# H12R10.net
KiCad netlist of a schematic drawn in EAGLE
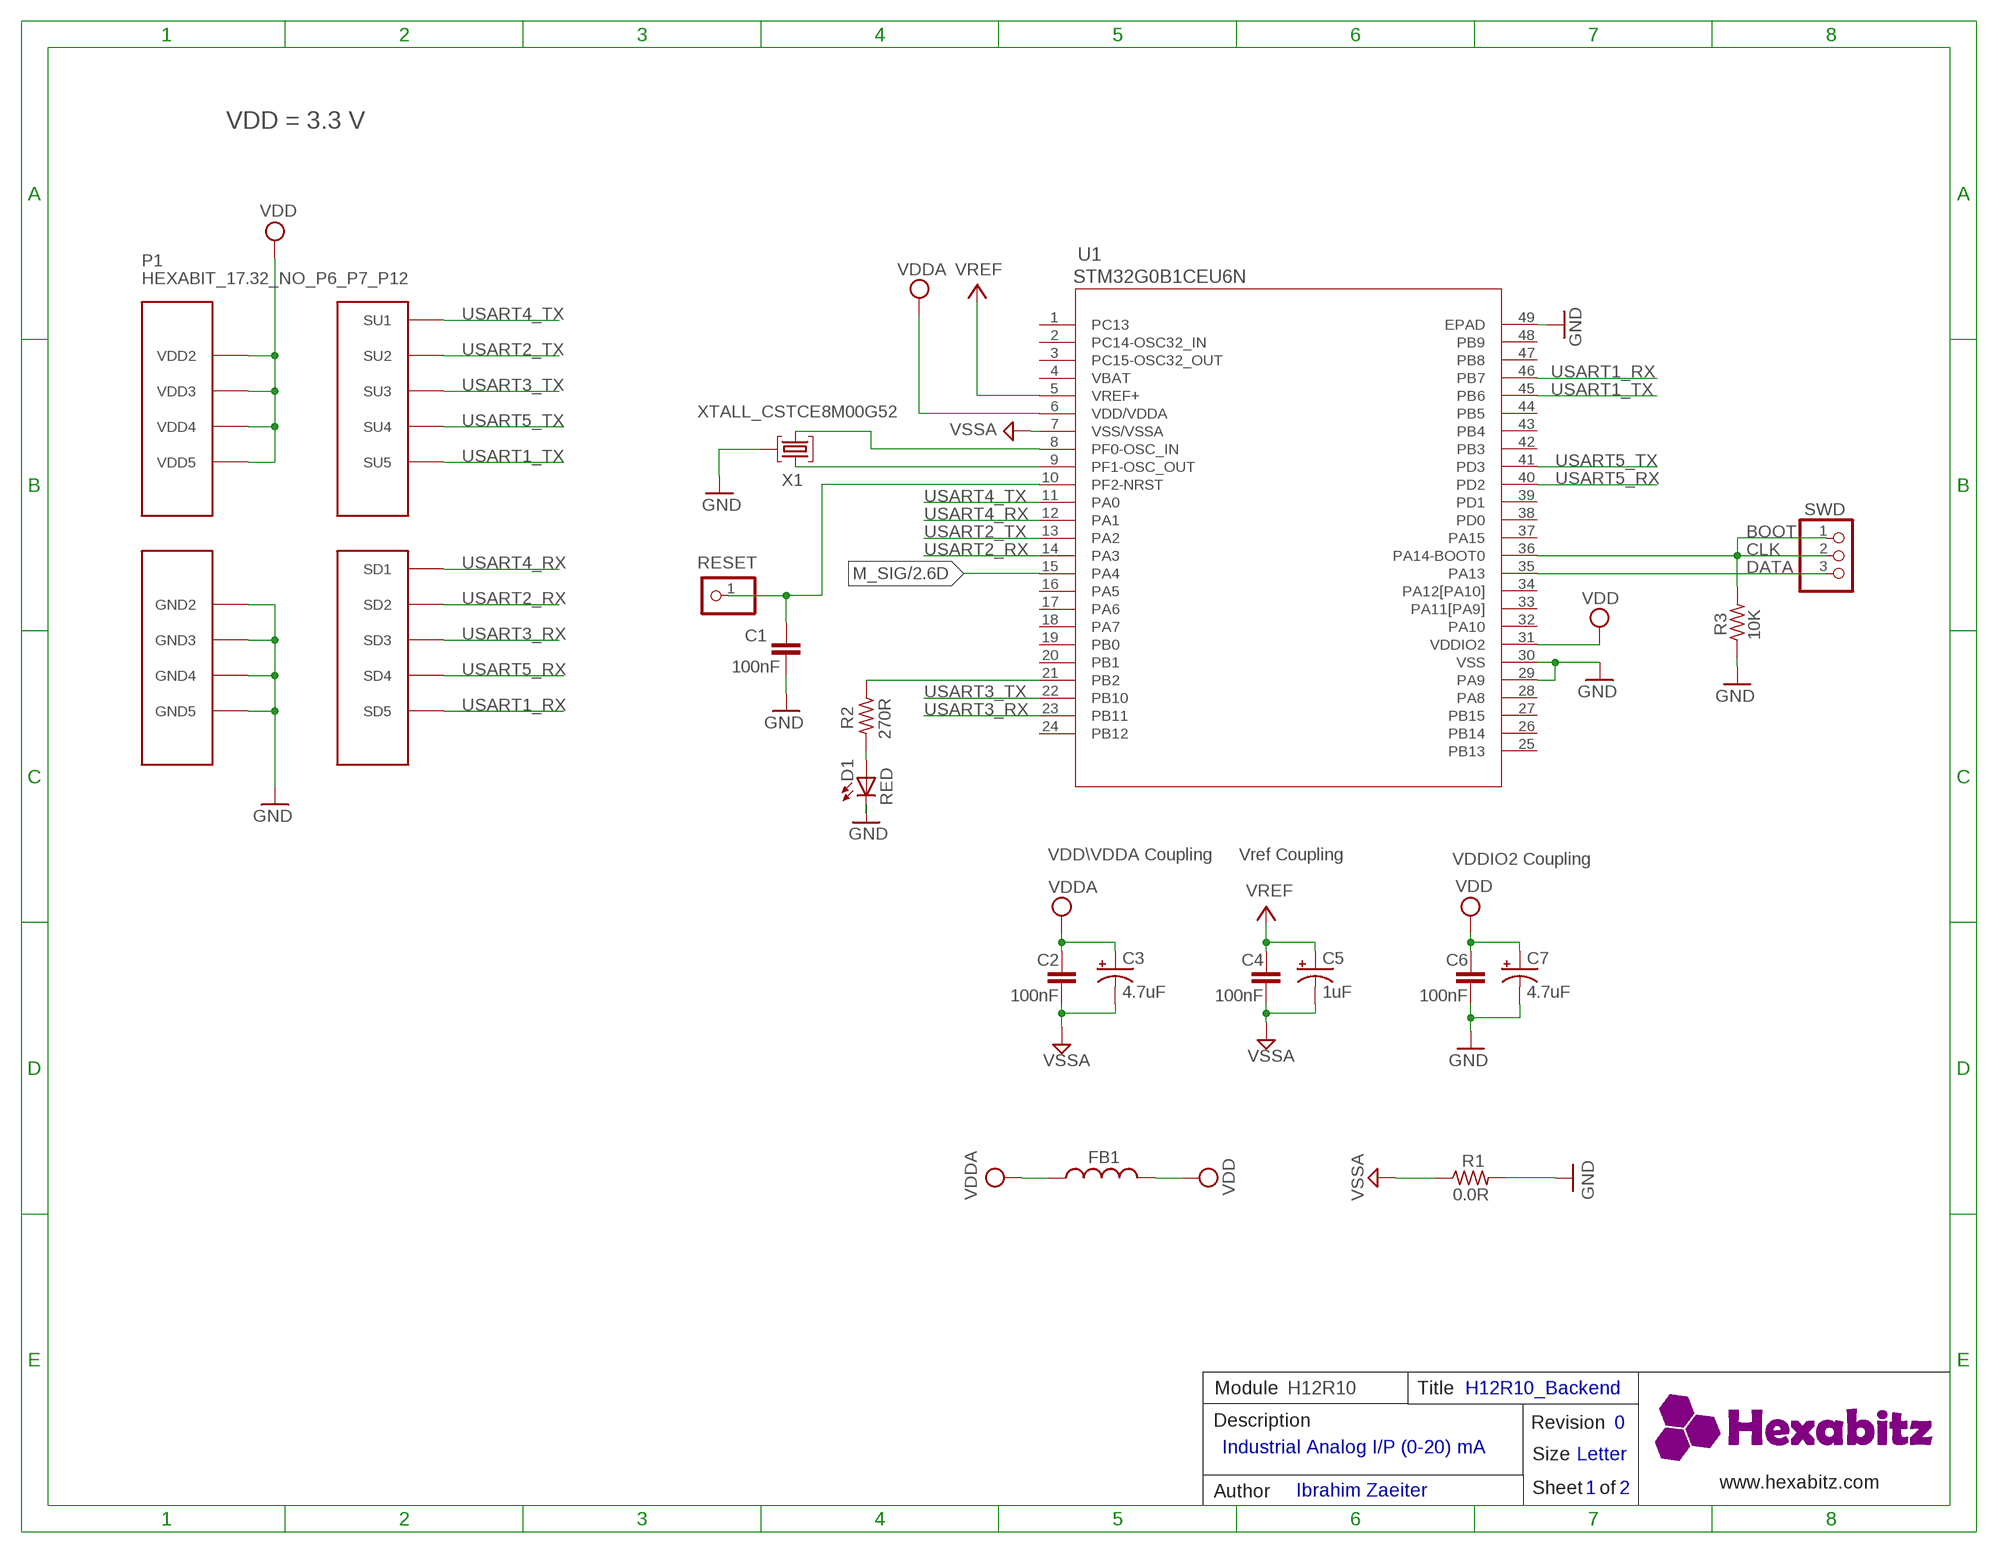
[diagram p0: schematic, sheet 1]
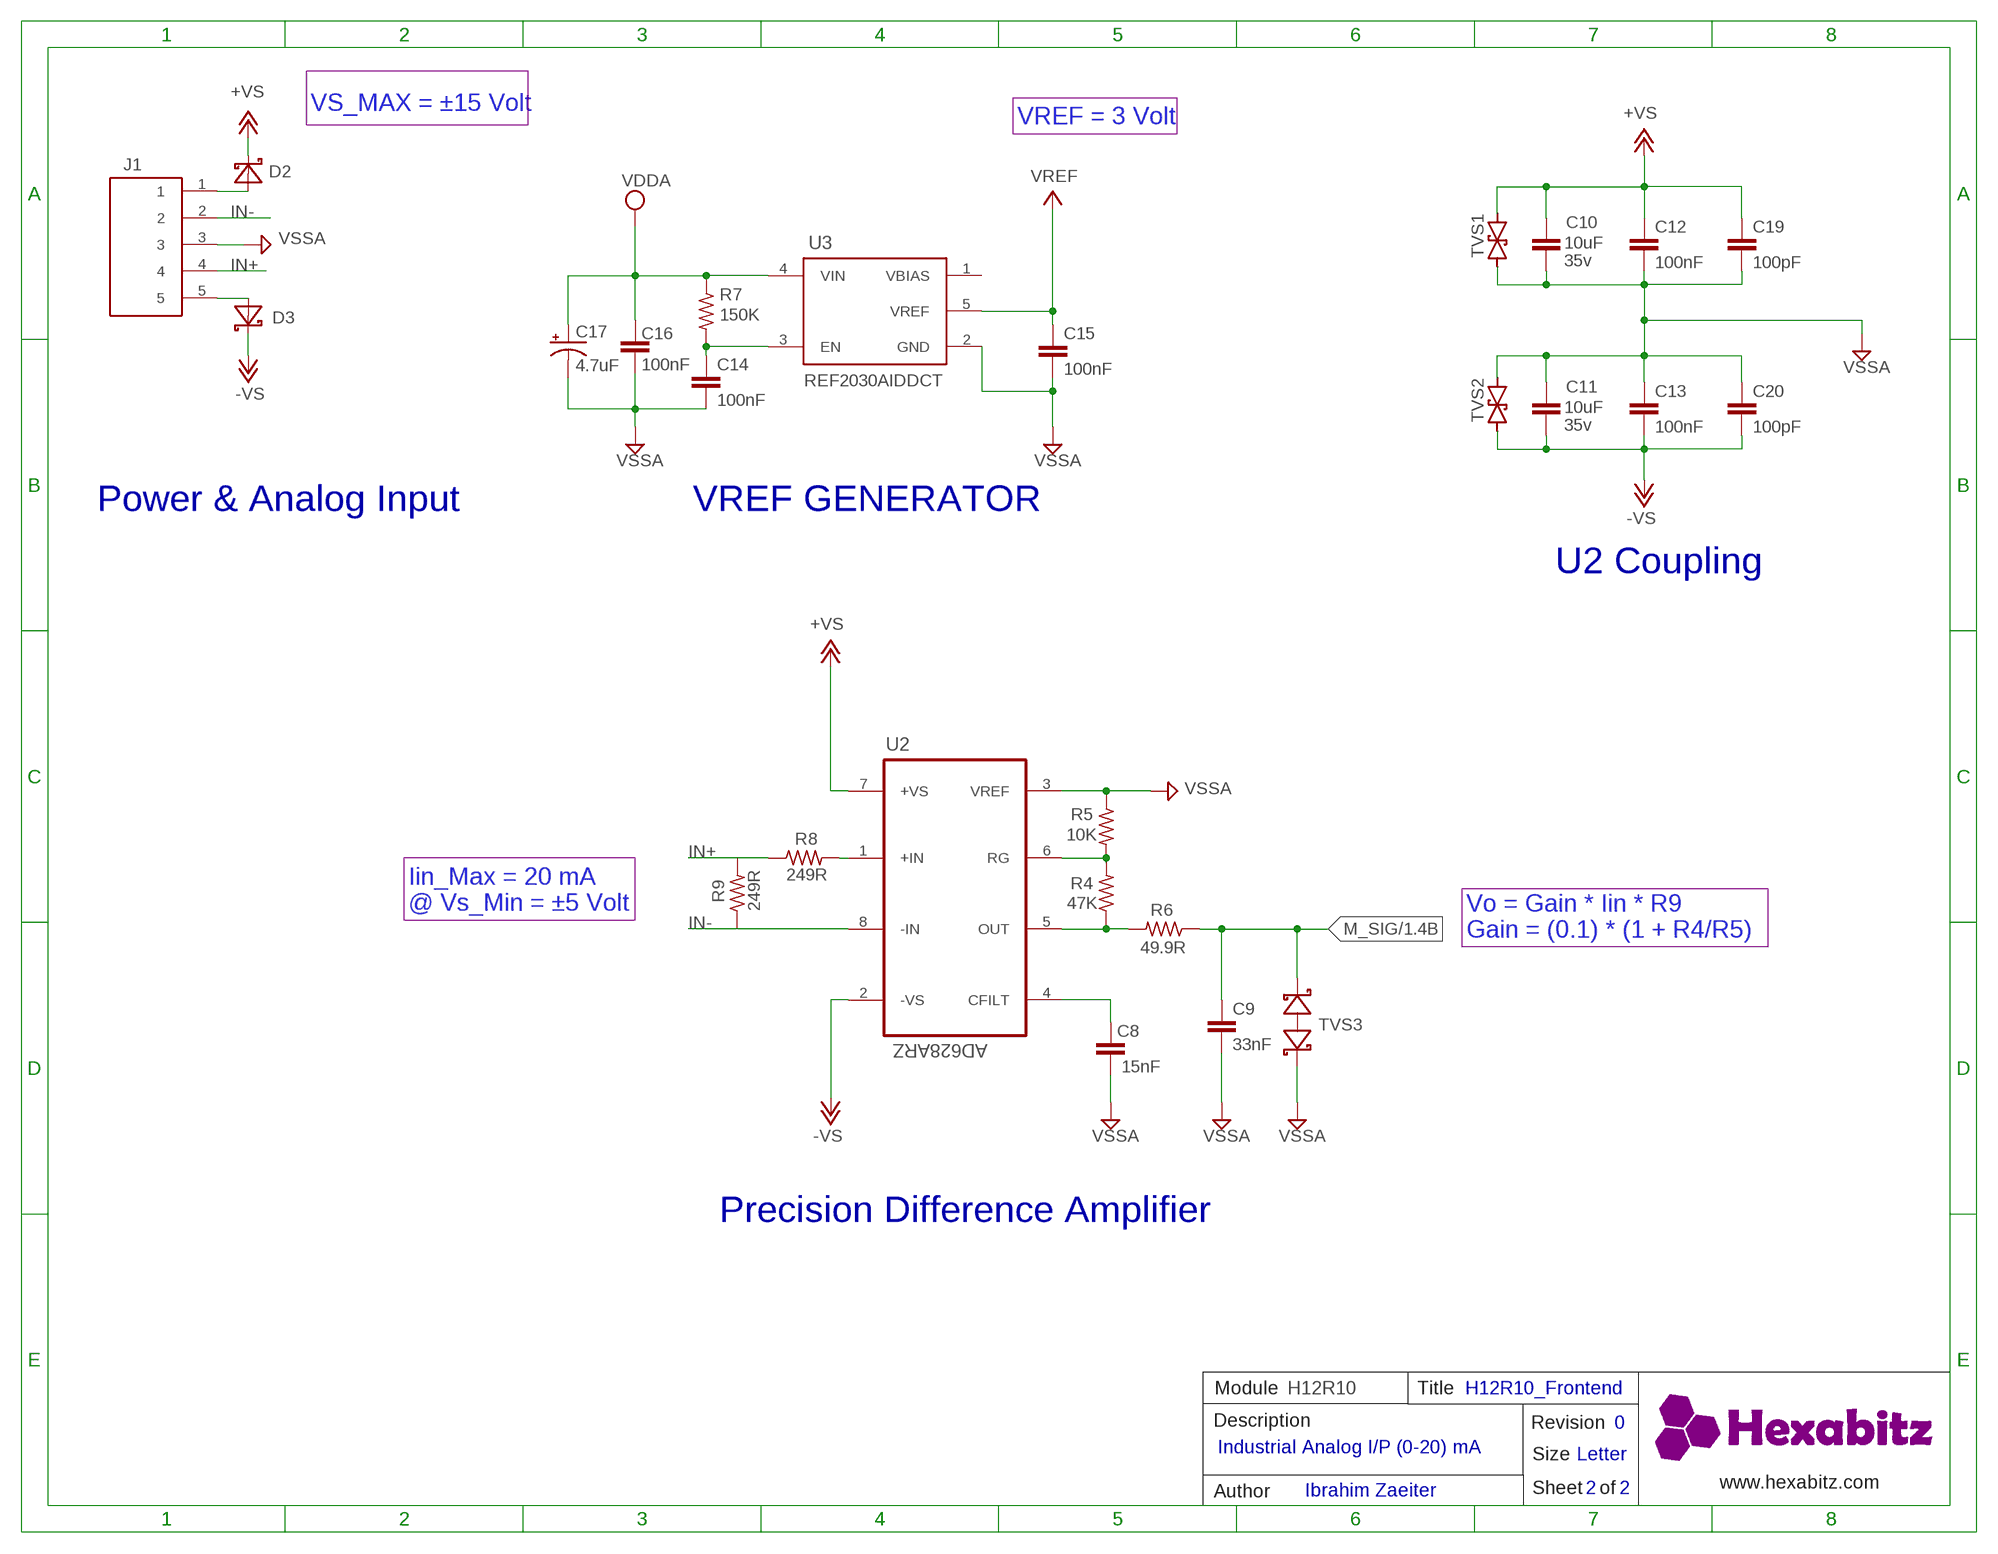
[diagram p1: schematic, sheet 2]

(export (version "E")
  (design (tool "Eeschema 10.0.6"))
  (components
    (comp (ref "C1")
      (value "100nF")
      (footprint "eagle-import:C-0603")
      (libsource (lib "eagle-import") (part "C-0603"))
    )
    (comp (ref "C2")
      (value "100nF")
      (footprint "eagle-import:C-0603")
      (libsource (lib "eagle-import") (part "C-0603"))
    )
    (comp (ref "C3")
      (value "4.7uF")
      (footprint "eagle-import:C-0805-POL")
      (libsource (lib "eagle-import") (part "C-0805-POL"))
    )
    (comp (ref "C4")
      (value "100nF")
      (footprint "eagle-import:C-0603")
      (libsource (lib "eagle-import") (part "C-0603"))
    )
    (comp (ref "C5")
      (value "1uF")
      (footprint "eagle-import:C-0805-POL")
      (libsource (lib "eagle-import") (part "C-0805-POL"))
    )
    (comp (ref "C6")
      (value "100nF")
      (footprint "eagle-import:C-0603")
      (libsource (lib "eagle-import") (part "C-0603"))
    )
    (comp (ref "C7")
      (value "4.7uF")
      (footprint "eagle-import:C-0805-POL")
      (libsource (lib "eagle-import") (part "C-0805-POL"))
    )
    (comp (ref "D1")
      (value "RED")
      (footprint "eagle-import:VLMS1300-GS08")
      (fields
        (field (name "MPN") "VLMS1300-GS08")
        (field (name "MFN") "Vishay")
        (field (name "MPN_1") "VLMS1300-GS08")
        (field (name "OCTOPART_URL") "https://octopart.com/vlms1300-gs08-vishay-21709201?r=sp&s=_gcP4_q8T1SC6PJQPTQ9yA")
      )
      (libsource (lib "eagle-import") (part "VLMS1300-GS08"))
    )
    (comp (ref "FB1")
      (value "FB-0603")
      (footprint "eagle-import:FB-0603")
      (libsource (lib "eagle-import") (part "FB-0603"))
    )
    (comp (ref "P1")
      (value "HEXABIT_17.32_NO_P6_P7_P12")
      (footprint "eagle-import:HEXABIT_17.32_NO_P6_P7_P12")
      (libsource (lib "eagle-import") (part "HEXABIT_?_NO_P6_P7_P1217.32"))
    )
    (comp (ref "R1")
      (value "0.0R")
      (footprint "eagle-import:R-0603")
      (libsource (lib "eagle-import") (part "R-0603"))
    )
    (comp (ref "R2")
      (value "270R")
      (footprint "eagle-import:R-0603")
      (libsource (lib "eagle-import") (part "R-0603"))
    )
    (comp (ref "R3")
      (value "10K")
      (footprint "eagle-import:R-0603")
      (libsource (lib "eagle-import") (part "R-0603"))
    )
    (comp (ref "RESET")
      (value "R")
      (footprint "eagle-import:1X01")
      (fields (field (name "MPN") "87227-1"))
      (libsource (lib "eagle-import") (part "PINHD-1X1"))
    )
    (comp (ref "SWD")
      (value "PINHD-1X3SWD")
      (footprint "eagle-import:SWD")
      (libsource (lib "eagle-import") (part "PINHD-1X3SWD"))
    )
    (comp (ref "U1")
      (value "STM32G0B1CEU6N")
      (footprint "eagle-import:HEXABITZ_ICS_QFN_B1CEU6_STM-L")
      (libsource (lib "eagle-import") (part "STM32G0B1CEU6N"))
    )
    (comp (ref "X1")
      (value "XTALL_CSTCE8M00G52")
      (footprint "eagle-import:XTALL_CSTCE8M00G52")
      (fields (field (name "MPN") "CSTCE8M00G52Z-R0"))
      (libsource (lib "eagle-import") (part "XTALL_CSTCE8M00G52"))
    )
    (comp (ref "C8")
      (value "15nF")
      (footprint "eagle-import:C-0603")
      (libsource (lib "eagle-import") (part "C-0603"))
    )
    (comp (ref "C9")
      (value "33nF")
      (footprint "eagle-import:C-0603")
      (libsource (lib "eagle-import") (part "C-0603"))
    )
    (comp (ref "C10")
      (value "C-0805")
      (footprint "eagle-import:C-0805")
      (fields
        (field (name "CAPACITANCE") "10uF")
        (field (name "MPN") "GRM21BR6YA106ME43K")
        (field (name "VOLTAGE_RATING") "35v")
      )
      (libsource (lib "eagle-import") (part "C-0805"))
    )
    (comp (ref "C11")
      (value "C-0805")
      (footprint "eagle-import:C-0805")
      (fields
        (field (name "CAPACITANCE") "10uF")
        (field (name "MPN") "GRM21BR6YA106ME43K")
        (field (name "VOLTAGE_RATING") "35v")
      )
      (libsource (lib "eagle-import") (part "C-0805"))
    )
    (comp (ref "C12")
      (value "100nF")
      (footprint "eagle-import:C-0603")
      (fields (field (name "MPN") "C1608X7R1H104K080AA"))
      (libsource (lib "eagle-import") (part "C-0603"))
    )
    (comp (ref "C13")
      (value "100nF")
      (footprint "eagle-import:C-0603")
      (fields (field (name "MPN") "C1608X7R1H104K080AA"))
      (libsource (lib "eagle-import") (part "C-0603"))
    )
    (comp (ref "C14")
      (value "100nF")
      (footprint "eagle-import:C-0603")
      (libsource (lib "eagle-import") (part "C-0603"))
    )
    (comp (ref "C15")
      (value "100nF")
      (footprint "eagle-import:C-0603")
      (libsource (lib "eagle-import") (part "C-0603"))
    )
    (comp (ref "C16")
      (value "100nF")
      (footprint "eagle-import:C-0603")
      (libsource (lib "eagle-import") (part "C-0603"))
    )
    (comp (ref "C17")
      (value "4.7uF")
      (footprint "eagle-import:C-0805-POL")
      (libsource (lib "eagle-import") (part "C-0805-POL"))
    )
    (comp (ref "C19")
      (value "100pF")
      (footprint "eagle-import:C-0603")
      (fields (field (name "MPN") "C1608X7R1H104K080AA"))
      (libsource (lib "eagle-import") (part "C-0603"))
    )
    (comp (ref "C20")
      (value "100pF")
      (footprint "eagle-import:C-0603")
      (fields (field (name "MPN") "C1608X7R1H104K080AA"))
      (libsource (lib "eagle-import") (part "C-0603"))
    )
    (comp (ref "D2")
      (value "DIOD-SOD-123")
      (footprint "eagle-import:SOD123")
      (libsource (lib "eagle-import") (part "DIOD-SOD-123"))
    )
    (comp (ref "D3")
      (value "DIOD-SOD-123")
      (footprint "eagle-import:SOD123")
      (libsource (lib "eagle-import") (part "DIOD-SOD-123"))
    )
    (comp (ref "J1")
      (value "1984646")
      (footprint "eagle-import:1984646")
      (fields (field (name "MOUSER_PART_NUMBER") "651-1984646"))
      (libsource (lib "eagle-import") (part "1984646"))
    )
    (comp (ref "R4")
      (value "47K")
      (footprint "eagle-import:R-0603")
      (libsource (lib "eagle-import") (part "R-0603"))
    )
    (comp (ref "R5")
      (value "10K")
      (footprint "eagle-import:R-0603")
      (libsource (lib "eagle-import") (part "R-0603"))
    )
    (comp (ref "R6")
      (value "49.9R")
      (footprint "eagle-import:R-0603")
      (libsource (lib "eagle-import") (part "R-0603"))
    )
    (comp (ref "R7")
      (value "150K")
      (footprint "eagle-import:R-0603")
      (libsource (lib "eagle-import") (part "R-0603"))
    )
    (comp (ref "R8")
      (value "249R")
      (footprint "eagle-import:R-0603")
      (libsource (lib "eagle-import") (part "R-0603"))
    )
    (comp (ref "R9")
      (value "249R")
      (footprint "eagle-import:R-0603")
      (libsource (lib "eagle-import") (part "R-0603"))
    )
    (comp (ref "TVS1")
      (value "SMBJ30CA")
      (footprint "eagle-import:DO214AA")
      (libsource (lib "eagle-import") (part "SMBJ30CA"))
    )
    (comp (ref "TVS2")
      (value "SMBJ30CA")
      (footprint "eagle-import:DO214AA")
      (libsource (lib "eagle-import") (part "SMBJ30CA"))
    )
    (comp (ref "TVS3")
      (value "BOURNS_CDSOD323-T03SCBOURNS_CDSOD323-T03SC_0_0")
      (footprint "eagle-import:BOURNS_CDSOD323-T03SC_0")
      (fields (field (name "MPN") "CDSOD323-T03SC"))
      (libsource (lib "eagle-import") (part "BOURNS_CDSOD323-T03SCBOURNS_CDSOD323-T03SC_0_0"))
    )
    (comp (ref "U2")
      (value "AD628ARZ")
      (footprint "eagle-import:SOIC127P600X175-8N")
      (libsource (lib "eagle-import") (part "AD628ARZ"))
    )
    (comp (ref "U3")
      (value "TEXAS_INSTRUMENTS_REF2033AIDDCRTEXAS_INSTRUMENTS_REF2033AIDDCR_0_2")
      (footprint "eagle-import:TEXAS_INSTRUMENTS_REF2033AIDDCR_2")
      (fields
        (field (name "MPN") "REF2033AIDDCR")
        (field (name "MPN_1") "REF2030AIDDCT")
        (field (name "OUTPUT_VOLTAGE") "1.5/3.0V")
      )
      (libsource (lib "eagle-import") (part "TEXAS_INSTRUMENTS_REF2033AIDDCRTEXAS_INSTRUMENTS_REF2033AIDDCR_0_2"))
    )
  )
  (nets
    (net (code "1") (name "+VS") (class "Default")
      (node (ref "C10") (pin "1") (pinfunction "1_1") (pintype "passive"))
      (node (ref "C12") (pin "1") (pinfunction "1_1") (pintype "passive"))
      (node (ref "C19") (pin "1") (pinfunction "1_1") (pintype "passive"))
      (node (ref "D2") (pin "2") (pinfunction "C_2") (pintype "passive"))
      (node (ref "TVS1") (pin "C") (pinfunction "2_C") (pintype "passive"))
      (node (ref "U2") (pin "7") (pinfunction "+VS_7") (pintype "power_in"))
    )
    (net (code "2") (name "-VS") (class "Default")
      (node (ref "C11") (pin "2") (pinfunction "2_2") (pintype "passive"))
      (node (ref "C13") (pin "2") (pinfunction "2_2") (pintype "passive"))
      (node (ref "C20") (pin "2") (pinfunction "2_2") (pintype "passive"))
      (node (ref "D3") (pin "2") (pinfunction "C_2") (pintype "passive"))
      (node (ref "TVS2") (pin "A") (pinfunction "1_A") (pintype "passive"))
      (node (ref "U2") (pin "2") (pinfunction "-VS_2") (pintype "power_in"))
    )
    (net (code "3") (name "CLK") (class "Default")
      (node (ref "R3") (pin "2") (pinfunction "2_2") (pintype "passive"))
      (node (ref "SWD") (pin "1") (pinfunction "1_1") (pintype "passive"))
      (node (ref "SWD") (pin "2") (pinfunction "2_2") (pintype "passive"))
      (node (ref "U1") (pin "36") (pinfunction "PA14-BOOT0_36") (pintype "bidirectional"))
    )
    (net (code "4") (name "DATA") (class "Default")
      (node (ref "SWD") (pin "3") (pinfunction "3_3") (pintype "passive"))
      (node (ref "U1") (pin "35") (pinfunction "PA13_35") (pintype "bidirectional"))
    )
    (net (code "5") (name "GND") (class "Default")
      (node (ref "C1") (pin "2") (pinfunction "2_2") (pintype "passive"))
      (node (ref "C6") (pin "2") (pinfunction "2_2") (pintype "passive"))
      (node (ref "C7") (pin "2") (pinfunction "-_2") (pintype "passive"))
      (node (ref "D1") (pin "C") (pinfunction "C_C") (pintype "passive"))
      (node (ref "P1") (pin "PAD_PD10") (pinfunction "GND4_PAD_PD10") (pintype "power_in"))
      (node (ref "P1") (pin "PAD_PD11") (pinfunction "GND5_PAD_PD11") (pintype "power_in"))
      (node (ref "P1") (pin "PAD_PD8") (pinfunction "GND2_PAD_PD8") (pintype "power_in"))
      (node (ref "P1") (pin "PAD_PD9") (pinfunction "GND3_PAD_PD9") (pintype "power_in"))
      (node (ref "R1") (pin "2") (pinfunction "2_2") (pintype "passive"))
      (node (ref "R3") (pin "1") (pinfunction "1_1") (pintype "passive"))
      (node (ref "U1") (pin "29") (pinfunction "PA9_29") (pintype "bidirectional"))
      (node (ref "U1") (pin "30") (pinfunction "VSS_30") (pintype "passive"))
      (node (ref "U1") (pin "49") (pinfunction "EPAD_49") (pintype "passive"))
      (node (ref "X1") (pin "P$2") (pinfunction "2_P$2") (pintype "passive"))
    )
    (net (code "6") (name "IN+") (class "Default")
      (node (ref "J1") (pin "4") (pinfunction "4_4") (pintype "bidirectional"))
      (node (ref "R8") (pin "1") (pinfunction "1_1") (pintype "passive"))
      (node (ref "R9") (pin "2") (pinfunction "2_2") (pintype "passive"))
    )
    (net (code "7") (name "IN-") (class "Default")
      (node (ref "J1") (pin "2") (pinfunction "2_2") (pintype "bidirectional"))
      (node (ref "R9") (pin "1") (pinfunction "1_1") (pintype "passive"))
      (node (ref "U2") (pin "8") (pinfunction "-IN_8") (pintype "input"))
    )
    (net (code "8") (name "M_SIG") (class "Default")
      (node (ref "C9") (pin "1") (pinfunction "1_1") (pintype "passive"))
      (node (ref "R6") (pin "1") (pinfunction "1_1") (pintype "passive"))
      (node (ref "TVS3") (pin "2") (pinfunction "C_2") (pintype "passive"))
      (node (ref "U1") (pin "15") (pinfunction "PA4_15") (pintype "bidirectional"))
    )
    (net (code "9") (name "Net-(D1-PadA)") (class "Default")
      (node (ref "D1") (pin "A") (pinfunction "A_A") (pintype "passive"))
      (node (ref "R2") (pin "2") (pinfunction "2_2") (pintype "passive"))
    )
    (net (code "10") (name "Net-(D2-A)") (class "Default")
      (node (ref "D2") (pin "1") (pinfunction "A_1") (pintype "passive"))
      (node (ref "J1") (pin "1") (pinfunction "1_1") (pintype "bidirectional"))
    )
    (net (code "11") (name "Net-(D3-A)") (class "Default")
      (node (ref "D3") (pin "1") (pinfunction "A_1") (pintype "passive"))
      (node (ref "J1") (pin "5") (pinfunction "5_5") (pintype "bidirectional"))
    )
    (net (code "12") (name "Net-(U1-PB2)") (class "Default")
      (node (ref "R2") (pin "1") (pinfunction "1_1") (pintype "passive"))
      (node (ref "U1") (pin "21") (pinfunction "PB2_21") (pintype "bidirectional"))
    )
    (net (code "13") (name "Net-(U1-PF0-OSC_IN)") (class "Default")
      (node (ref "U1") (pin "8") (pinfunction "PF0-OSC_IN_8") (pintype "bidirectional"))
      (node (ref "X1") (pin "P$3") (pinfunction "3_P$3") (pintype "passive"))
    )
    (net (code "14") (name "Net-(U1-PF1-OSC_OUT)") (class "Default")
      (node (ref "U1") (pin "9") (pinfunction "PF1-OSC_OUT_9") (pintype "bidirectional"))
      (node (ref "X1") (pin "P$1") (pinfunction "1_P$1") (pintype "passive"))
    )
    (net (code "15") (name "Net-(U1-PF2-NRST)") (class "Default")
      (node (ref "C1") (pin "1") (pinfunction "1_1") (pintype "passive"))
      (node (ref "RESET") (pin "1") (pinfunction "1_1") (pintype "passive"))
      (node (ref "U1") (pin "10") (pinfunction "PF2-NRST_10") (pintype "bidirectional"))
    )
    (net (code "16") (name "Net-(U2-+IN)") (class "Default")
      (node (ref "R8") (pin "2") (pinfunction "2_2") (pintype "passive"))
      (node (ref "U2") (pin "1") (pinfunction "+IN_1") (pintype "input"))
    )
    (net (code "17") (name "Net-(U2-CFILT)") (class "Default")
      (node (ref "C8") (pin "1") (pinfunction "1_1") (pintype "passive"))
      (node (ref "U2") (pin "4") (pinfunction "CFILT_4") (pintype "passive"))
    )
    (net (code "18") (name "Net-(U2-OUT)") (class "Default")
      (node (ref "R4") (pin "1") (pinfunction "1_1") (pintype "passive"))
      (node (ref "R6") (pin "2") (pinfunction "2_2") (pintype "passive"))
      (node (ref "U2") (pin "5") (pinfunction "OUT_5") (pintype "output"))
    )
    (net (code "19") (name "Net-(U2-RG)") (class "Default")
      (node (ref "R4") (pin "2") (pinfunction "2_2") (pintype "passive"))
      (node (ref "R5") (pin "2") (pinfunction "2_2") (pintype "passive"))
      (node (ref "U2") (pin "6") (pinfunction "RG_6") (pintype "passive"))
    )
    (net (code "20") (name "Net-(U3-EN)") (class "Default")
      (node (ref "C14") (pin "1") (pinfunction "1_1") (pintype "passive"))
      (node (ref "R7") (pin "2") (pinfunction "2_2") (pintype "passive"))
      (node (ref "U3") (pin "3") (pinfunction "EN_3") (pintype "input"))
    )
    (net (code "21") (name "USART1_RX") (class "Default")
      (node (ref "P1") (pin "PAD_PD5") (pinfunction "SD5_PAD_PD5") (pintype "bidirectional"))
      (node (ref "U1") (pin "46") (pinfunction "PB7_46") (pintype "bidirectional"))
    )
    (net (code "22") (name "USART1_TX") (class "Default")
      (node (ref "P1") (pin "PAD_PU5") (pinfunction "SU5_PAD_PU5") (pintype "bidirectional"))
      (node (ref "U1") (pin "45") (pinfunction "PB6_45") (pintype "bidirectional"))
    )
    (net (code "23") (name "USART2_RX") (class "Default")
      (node (ref "P1") (pin "PAD_PD2") (pinfunction "SD2_PAD_PD2") (pintype "bidirectional"))
      (node (ref "U1") (pin "14") (pinfunction "PA3_14") (pintype "bidirectional"))
    )
    (net (code "24") (name "USART2_TX") (class "Default")
      (node (ref "P1") (pin "PAD_PU2") (pinfunction "SU2_PAD_PU2") (pintype "bidirectional"))
      (node (ref "U1") (pin "13") (pinfunction "PA2_13") (pintype "bidirectional"))
    )
    (net (code "25") (name "USART3_RX") (class "Default")
      (node (ref "P1") (pin "PAD_PD3") (pinfunction "SD3_PAD_PD3") (pintype "bidirectional"))
      (node (ref "U1") (pin "23") (pinfunction "PB11_23") (pintype "bidirectional"))
    )
    (net (code "26") (name "USART3_TX") (class "Default")
      (node (ref "P1") (pin "PAD_PU3") (pinfunction "SU3_PAD_PU3") (pintype "bidirectional"))
      (node (ref "U1") (pin "22") (pinfunction "PB10_22") (pintype "bidirectional"))
    )
    (net (code "27") (name "USART4_RX") (class "Default")
      (node (ref "P1") (pin "PAD_PD1") (pinfunction "SD1_PAD_PD1") (pintype "bidirectional"))
      (node (ref "U1") (pin "12") (pinfunction "PA1_12") (pintype "bidirectional"))
    )
    (net (code "28") (name "USART4_TX") (class "Default")
      (node (ref "P1") (pin "PAD_PU1") (pinfunction "SU1_PAD_PU1") (pintype "bidirectional"))
      (node (ref "U1") (pin "11") (pinfunction "PA0_11") (pintype "bidirectional"))
    )
    (net (code "29") (name "USART5_RX") (class "Default")
      (node (ref "P1") (pin "PAD_PD4") (pinfunction "SD4_PAD_PD4") (pintype "bidirectional"))
      (node (ref "U1") (pin "40") (pinfunction "PD2_40") (pintype "bidirectional"))
    )
    (net (code "30") (name "USART5_TX") (class "Default")
      (node (ref "P1") (pin "PAD_PU4") (pinfunction "SU4_PAD_PU4") (pintype "bidirectional"))
      (node (ref "U1") (pin "41") (pinfunction "PD3_41") (pintype "bidirectional"))
    )
    (net (code "31") (name "VBAT") (class "Default")
      (node (ref "U1") (pin "4") (pinfunction "VBAT_4") (pintype "power_in"))
    )
    (net (code "32") (name "VBIAS") (class "Default")
      (node (ref "U3") (pin "1") (pinfunction "VBIAS_1") (pintype "power_in"))
    )
    (net (code "33") (name "VDD") (class "Default")
      (node (ref "C6") (pin "1") (pinfunction "1_1") (pintype "passive"))
      (node (ref "C7") (pin "1") (pinfunction "+_1") (pintype "passive"))
      (node (ref "FB1") (pin "2") (pinfunction "2_2") (pintype "passive"))
      (node (ref "P1") (pin "PAD_PU10") (pinfunction "VDD4_PAD_PU10") (pintype "power_in"))
      (node (ref "P1") (pin "PAD_PU11") (pinfunction "VDD5_PAD_PU11") (pintype "power_in"))
      (node (ref "P1") (pin "PAD_PU8") (pinfunction "VDD2_PAD_PU8") (pintype "power_in"))
      (node (ref "P1") (pin "PAD_PU9") (pinfunction "VDD3_PAD_PU9") (pintype "power_in"))
      (node (ref "U1") (pin "31") (pinfunction "VDDIO2_31") (pintype "power_in"))
    )
    (net (code "34") (name "VDDA") (class "Default")
      (node (ref "C16") (pin "1") (pinfunction "1_1") (pintype "passive"))
      (node (ref "C17") (pin "1") (pinfunction "+_1") (pintype "passive"))
      (node (ref "C2") (pin "1") (pinfunction "1_1") (pintype "passive"))
      (node (ref "C3") (pin "1") (pinfunction "+_1") (pintype "passive"))
      (node (ref "FB1") (pin "1") (pinfunction "1_1") (pintype "passive"))
      (node (ref "R7") (pin "1") (pinfunction "1_1") (pintype "passive"))
      (node (ref "U1") (pin "6") (pinfunction "VDD/VDDA_6") (pintype "power_in"))
      (node (ref "U3") (pin "4") (pinfunction "VIN_4") (pintype "power_in"))
    )
    (net (code "35") (name "VREF") (class "Default")
      (node (ref "C15") (pin "1") (pinfunction "1_1") (pintype "passive"))
      (node (ref "C4") (pin "1") (pinfunction "1_1") (pintype "passive"))
      (node (ref "C5") (pin "1") (pinfunction "+_1") (pintype "passive"))
      (node (ref "U1") (pin "5") (pinfunction "VREF+_5") (pintype "power_in"))
      (node (ref "U3") (pin "5") (pinfunction "VREF_5") (pintype "power_in"))
    )
    (net (code "36") (name "VSSA") (class "Default")
      (node (ref "C10") (pin "2") (pinfunction "2_2") (pintype "passive"))
      (node (ref "C11") (pin "1") (pinfunction "1_1") (pintype "passive"))
      (node (ref "C12") (pin "2") (pinfunction "2_2") (pintype "passive"))
      (node (ref "C13") (pin "1") (pinfunction "1_1") (pintype "passive"))
      (node (ref "C14") (pin "2") (pinfunction "2_2") (pintype "passive"))
      (node (ref "C15") (pin "2") (pinfunction "2_2") (pintype "passive"))
      (node (ref "C16") (pin "2") (pinfunction "2_2") (pintype "passive"))
      (node (ref "C17") (pin "2") (pinfunction "-_2") (pintype "passive"))
      (node (ref "C19") (pin "2") (pinfunction "2_2") (pintype "passive"))
      (node (ref "C2") (pin "2") (pinfunction "2_2") (pintype "passive"))
      (node (ref "C20") (pin "1") (pinfunction "1_1") (pintype "passive"))
      (node (ref "C3") (pin "2") (pinfunction "-_2") (pintype "passive"))
      (node (ref "C4") (pin "2") (pinfunction "2_2") (pintype "passive"))
      (node (ref "C5") (pin "2") (pinfunction "-_2") (pintype "passive"))
      (node (ref "C8") (pin "2") (pinfunction "2_2") (pintype "passive"))
      (node (ref "C9") (pin "2") (pinfunction "2_2") (pintype "passive"))
      (node (ref "J1") (pin "3") (pinfunction "3_3") (pintype "bidirectional"))
      (node (ref "R1") (pin "1") (pinfunction "1_1") (pintype "passive"))
      (node (ref "R5") (pin "1") (pinfunction "1_1") (pintype "passive"))
      (node (ref "TVS1") (pin "A") (pinfunction "1_A") (pintype "passive"))
      (node (ref "TVS2") (pin "C") (pinfunction "2_C") (pintype "passive"))
      (node (ref "TVS3") (pin "1") (pinfunction "A_1") (pintype "passive"))
      (node (ref "U1") (pin "7") (pinfunction "VSS/VSSA_7") (pintype "passive"))
      (node (ref "U2") (pin "3") (pinfunction "VREF_3") (pintype "passive"))
      (node (ref "U3") (pin "2") (pinfunction "GND_2") (pintype "power_in"))
    )
    (net (code "37") (name "unconnected-(U1-PA5-Pad16)") (class "Default")
      (node (ref "U1") (pin "16") (pinfunction "PA5_16") (pintype "bidirectional"))
    )
    (net (code "38") (name "unconnected-(U1-PA6-Pad17)") (class "Default")
      (node (ref "U1") (pin "17") (pinfunction "PA6_17") (pintype "bidirectional"))
    )
    (net (code "39") (name "unconnected-(U1-PA7-Pad18)") (class "Default")
      (node (ref "U1") (pin "18") (pinfunction "PA7_18") (pintype "bidirectional"))
    )
    (net (code "40") (name "unconnected-(U1-PA8-Pad28)") (class "Default")
      (node (ref "U1") (pin "28") (pinfunction "PA8_28") (pintype "bidirectional"))
    )
    (net (code "41") (name "unconnected-(U1-PA10-Pad32)") (class "Default")
      (node (ref "U1") (pin "32") (pinfunction "PA10_32") (pintype "bidirectional"))
    )
    (net (code "42") (name "unconnected-(U1-PA11[PA9]-Pad33)") (class "Default")
      (node (ref "U1") (pin "33") (pinfunction "PA11[PA9]_33") (pintype "bidirectional"))
    )
    (net (code "43") (name "unconnected-(U1-PA12[PA10]-Pad34)") (class "Default")
      (node (ref "U1") (pin "34") (pinfunction "PA12[PA10]_34") (pintype "bidirectional"))
    )
    (net (code "44") (name "unconnected-(U1-PA15-Pad37)") (class "Default")
      (node (ref "U1") (pin "37") (pinfunction "PA15_37") (pintype "bidirectional"))
    )
    (net (code "45") (name "unconnected-(U1-PB0-Pad19)") (class "Default")
      (node (ref "U1") (pin "19") (pinfunction "PB0_19") (pintype "bidirectional"))
    )
    (net (code "46") (name "unconnected-(U1-PB1-Pad20)") (class "Default")
      (node (ref "U1") (pin "20") (pinfunction "PB1_20") (pintype "bidirectional"))
    )
    (net (code "47") (name "unconnected-(U1-PB3-Pad42)") (class "Default")
      (node (ref "U1") (pin "42") (pinfunction "PB3_42") (pintype "bidirectional"))
    )
    (net (code "48") (name "unconnected-(U1-PB4-Pad43)") (class "Default")
      (node (ref "U1") (pin "43") (pinfunction "PB4_43") (pintype "bidirectional"))
    )
    (net (code "49") (name "unconnected-(U1-PB5-Pad44)") (class "Default")
      (node (ref "U1") (pin "44") (pinfunction "PB5_44") (pintype "bidirectional"))
    )
    (net (code "50") (name "unconnected-(U1-PB8-Pad47)") (class "Default")
      (node (ref "U1") (pin "47") (pinfunction "PB8_47") (pintype "bidirectional"))
    )
    (net (code "51") (name "unconnected-(U1-PB9-Pad48)") (class "Default")
      (node (ref "U1") (pin "48") (pinfunction "PB9_48") (pintype "bidirectional"))
    )
    (net (code "52") (name "unconnected-(U1-PB12-Pad24)") (class "Default")
      (node (ref "U1") (pin "24") (pinfunction "PB12_24") (pintype "bidirectional"))
    )
    (net (code "53") (name "unconnected-(U1-PB13-Pad25)") (class "Default")
      (node (ref "U1") (pin "25") (pinfunction "PB13_25") (pintype "bidirectional"))
    )
    (net (code "54") (name "unconnected-(U1-PB14-Pad26)") (class "Default")
      (node (ref "U1") (pin "26") (pinfunction "PB14_26") (pintype "bidirectional"))
    )
    (net (code "55") (name "unconnected-(U1-PB15-Pad27)") (class "Default")
      (node (ref "U1") (pin "27") (pinfunction "PB15_27") (pintype "bidirectional"))
    )
    (net (code "56") (name "unconnected-(U1-PC13-Pad1)") (class "Default")
      (node (ref "U1") (pin "1") (pinfunction "PC13_1") (pintype "bidirectional"))
    )
    (net (code "57") (name "unconnected-(U1-PC14-OSC32_IN-Pad2)") (class "Default")
      (node (ref "U1") (pin "2") (pinfunction "PC14-OSC32_IN_2") (pintype "bidirectional"))
    )
    (net (code "58") (name "unconnected-(U1-PC15-OSC32_OUT-Pad3)") (class "Default")
      (node (ref "U1") (pin "3") (pinfunction "PC15-OSC32_OUT_3") (pintype "bidirectional"))
    )
    (net (code "59") (name "unconnected-(U1-PD0-Pad38)") (class "Default")
      (node (ref "U1") (pin "38") (pinfunction "PD0_38") (pintype "bidirectional"))
    )
    (net (code "60") (name "unconnected-(U1-PD1-Pad39)") (class "Default")
      (node (ref "U1") (pin "39") (pinfunction "PD1_39") (pintype "bidirectional"))
    )
  )
)
